# 2020_Light_sensor_-_Schematic.net
KiCad netlist of a schematic drawn in EasyEDA
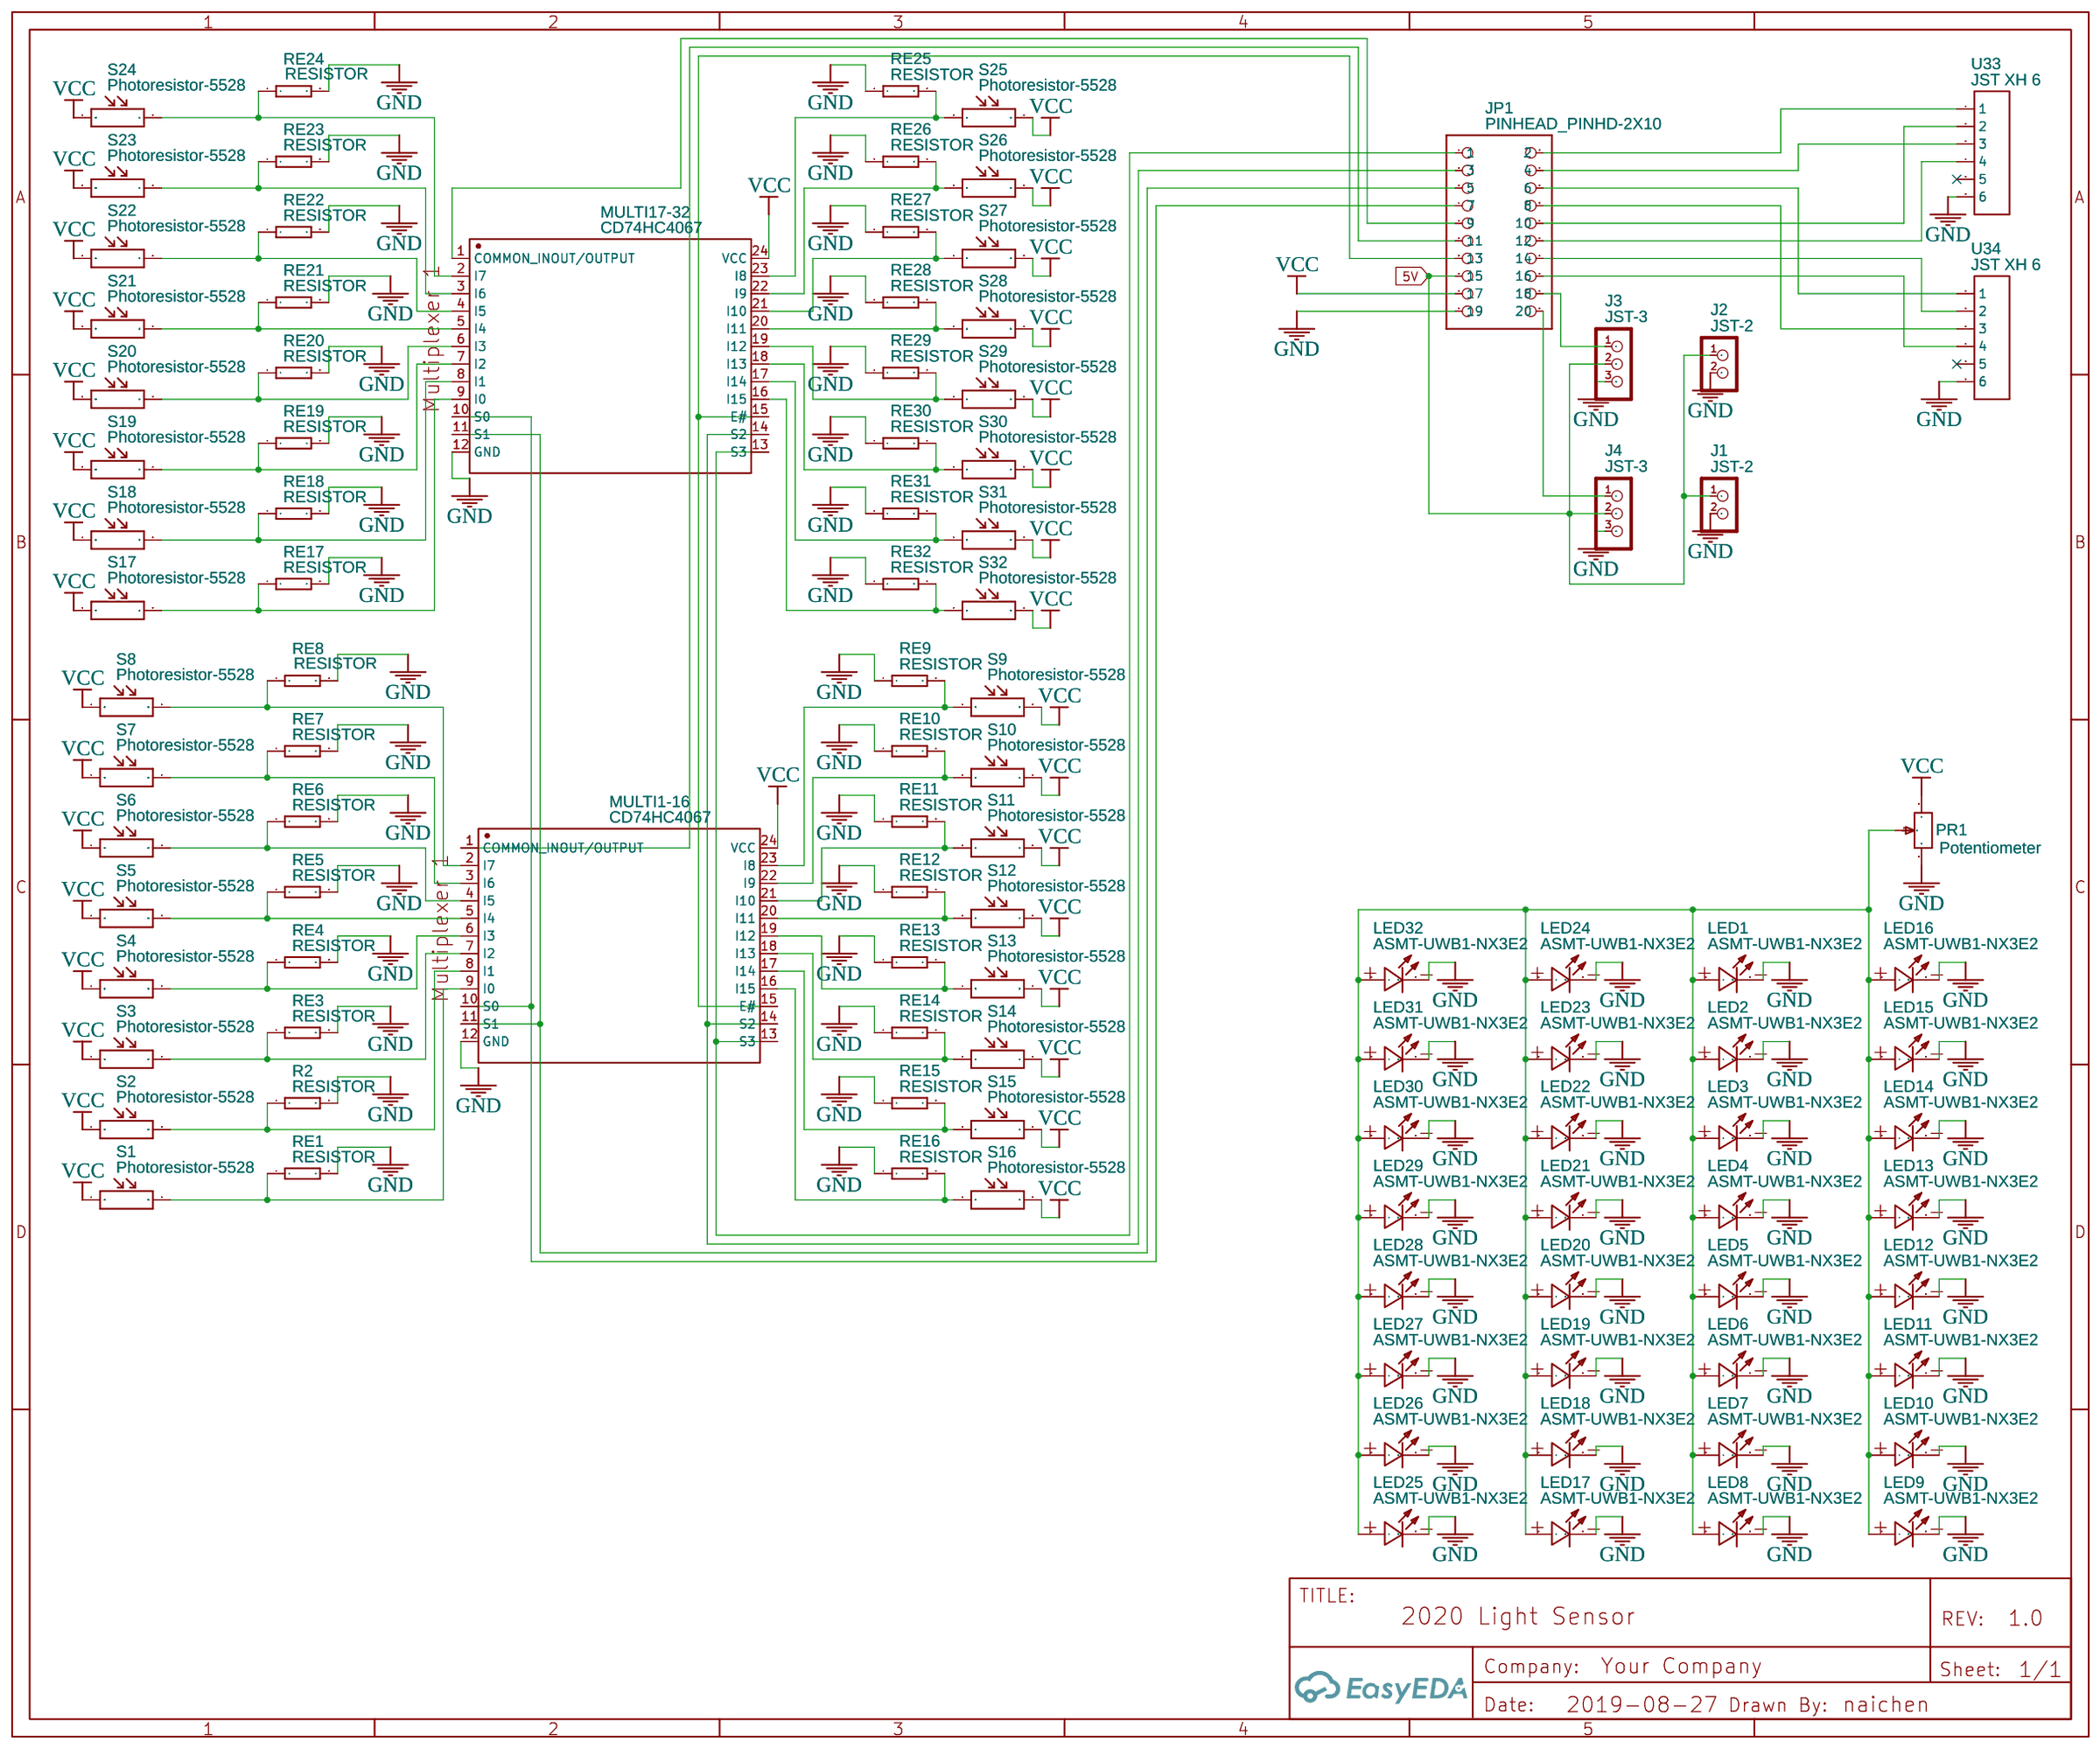
[diagram p0: schematic sheet]

(export (version "E")
  (design (tool "Eeschema 10.0.6"))
  (components
    (comp (ref "J1") (value "JST-2") (libsource (lib "") (part "JST-2")))
    (comp (ref "J2") (value "JST-2") (libsource (lib "") (part "JST-2")))
    (comp (ref "J3") (value "JST-3") (libsource (lib "") (part "JST-3")))
    (comp (ref "J4") (value "JST-3") (libsource (lib "") (part "JST-3")))
    (comp (ref "JP1") (value "PINHEAD_PINHD-2X10") (libsource (lib "") (part "Unknown_845_125")))
    (comp (ref "LED1")
      (value "ASMT-UWB1-NX3E2")
      (fields
        (field (name "BOM_Manufacturer Part") "ASMT-BG20-AS000")
        (field (name "BOM_Supplier Part") "C188684")
      )
      (libsource (lib "") (part "Unknown_975_550"))
    )
    (comp (ref "LED2")
      (value "ASMT-UWB1-NX3E2")
      (fields
        (field (name "BOM_Manufacturer Part") "ASMT-BG20-AS000")
        (field (name "BOM_Supplier Part") "C188684")
      )
      (libsource (lib "") (part "Unknown_975_595"))
    )
    (comp (ref "LED3")
      (value "ASMT-UWB1-NX3E2")
      (fields
        (field (name "BOM_Manufacturer Part") "ASMT-BG20-AS000")
        (field (name "BOM_Supplier Part") "C188684")
      )
      (libsource (lib "") (part "Unknown_975_640"))
    )
    (comp (ref "LED4")
      (value "ASMT-UWB1-NX3E2")
      (fields
        (field (name "BOM_Manufacturer Part") "ASMT-BG20-AS000")
        (field (name "BOM_Supplier Part") "C188684")
      )
      (libsource (lib "") (part "Unknown_975_685"))
    )
    (comp (ref "LED5")
      (value "ASMT-UWB1-NX3E2")
      (fields
        (field (name "BOM_Manufacturer Part") "ASMT-BG20-AS000")
        (field (name "BOM_Supplier Part") "C188684")
      )
      (libsource (lib "") (part "Unknown_975_730"))
    )
    (comp (ref "LED6")
      (value "ASMT-UWB1-NX3E2")
      (fields
        (field (name "BOM_Manufacturer Part") "ASMT-BG20-AS000")
        (field (name "BOM_Supplier Part") "C188684")
      )
      (libsource (lib "") (part "Unknown_975_775"))
    )
    (comp (ref "LED7")
      (value "ASMT-UWB1-NX3E2")
      (fields
        (field (name "BOM_Manufacturer Part") "ASMT-BG20-AS000")
        (field (name "BOM_Supplier Part") "C188684")
      )
      (libsource (lib "") (part "Unknown_975_820"))
    )
    (comp (ref "LED8")
      (value "ASMT-UWB1-NX3E2")
      (fields
        (field (name "BOM_Manufacturer Part") "ASMT-BG20-AS000")
        (field (name "BOM_Supplier Part") "C188684")
      )
      (libsource (lib "") (part "Unknown_975_865"))
    )
    (comp (ref "LED9")
      (value "ASMT-UWB1-NX3E2")
      (fields
        (field (name "BOM_Manufacturer Part") "ASMT-BG20-AS000")
        (field (name "BOM_Supplier Part") "C188684")
      )
      (libsource (lib "") (part "Unknown_1075_865"))
    )
    (comp (ref "LED10")
      (value "ASMT-UWB1-NX3E2")
      (fields
        (field (name "BOM_Manufacturer Part") "ASMT-BG20-AS000")
        (field (name "BOM_Supplier Part") "C188684")
      )
      (libsource (lib "") (part "Unknown_1075_820"))
    )
    (comp (ref "LED11")
      (value "ASMT-UWB1-NX3E2")
      (fields
        (field (name "BOM_Manufacturer Part") "ASMT-BG20-AS000")
        (field (name "BOM_Supplier Part") "C188684")
      )
      (libsource (lib "") (part "Unknown_1075_775"))
    )
    (comp (ref "LED12")
      (value "ASMT-UWB1-NX3E2")
      (fields
        (field (name "BOM_Manufacturer Part") "ASMT-BG20-AS000")
        (field (name "BOM_Supplier Part") "C188684")
      )
      (libsource (lib "") (part "Unknown_1075_730"))
    )
    (comp (ref "LED13")
      (value "ASMT-UWB1-NX3E2")
      (fields
        (field (name "BOM_Manufacturer Part") "ASMT-BG20-AS000")
        (field (name "BOM_Supplier Part") "C188684")
      )
      (libsource (lib "") (part "Unknown_1075_685"))
    )
    (comp (ref "LED14")
      (value "ASMT-UWB1-NX3E2")
      (fields
        (field (name "BOM_Manufacturer Part") "ASMT-BG20-AS000")
        (field (name "BOM_Supplier Part") "C188684")
      )
      (libsource (lib "") (part "Unknown_1075_640"))
    )
    (comp (ref "LED15")
      (value "ASMT-UWB1-NX3E2")
      (fields
        (field (name "BOM_Manufacturer Part") "ASMT-BG20-AS000")
        (field (name "BOM_Supplier Part") "C188684")
      )
      (libsource (lib "") (part "Unknown_1075_595"))
    )
    (comp (ref "LED16")
      (value "ASMT-UWB1-NX3E2")
      (fields
        (field (name "BOM_Manufacturer Part") "ASMT-BG20-AS000")
        (field (name "BOM_Supplier Part") "C188684")
      )
      (libsource (lib "") (part "Unknown_1075_550"))
    )
    (comp (ref "LED17")
      (value "ASMT-UWB1-NX3E2")
      (fields
        (field (name "BOM_Manufacturer Part") "ASMT-BG20-AS000")
        (field (name "BOM_Supplier Part") "C188684")
      )
      (libsource (lib "") (part "Unknown_880_865"))
    )
    (comp (ref "LED18")
      (value "ASMT-UWB1-NX3E2")
      (fields
        (field (name "BOM_Manufacturer Part") "ASMT-BG20-AS000")
        (field (name "BOM_Supplier Part") "C188684")
      )
      (libsource (lib "") (part "Unknown_880_820"))
    )
    (comp (ref "LED19")
      (value "ASMT-UWB1-NX3E2")
      (fields
        (field (name "BOM_Manufacturer Part") "ASMT-BG20-AS000")
        (field (name "BOM_Supplier Part") "C188684")
      )
      (libsource (lib "") (part "Unknown_880_775"))
    )
    (comp (ref "LED20")
      (value "ASMT-UWB1-NX3E2")
      (fields
        (field (name "BOM_Manufacturer Part") "ASMT-BG20-AS000")
        (field (name "BOM_Supplier Part") "C188684")
      )
      (libsource (lib "") (part "Unknown_880_730"))
    )
    (comp (ref "LED21")
      (value "ASMT-UWB1-NX3E2")
      (fields
        (field (name "BOM_Manufacturer Part") "ASMT-BG20-AS000")
        (field (name "BOM_Supplier Part") "C188684")
      )
      (libsource (lib "") (part "Unknown_880_685"))
    )
    (comp (ref "LED22")
      (value "ASMT-UWB1-NX3E2")
      (fields
        (field (name "BOM_Manufacturer Part") "ASMT-BG20-AS000")
        (field (name "BOM_Supplier Part") "C188684")
      )
      (libsource (lib "") (part "Unknown_880_640"))
    )
    (comp (ref "LED23")
      (value "ASMT-UWB1-NX3E2")
      (fields
        (field (name "BOM_Manufacturer Part") "ASMT-BG20-AS000")
        (field (name "BOM_Supplier Part") "C188684")
      )
      (libsource (lib "") (part "Unknown_880_595"))
    )
    (comp (ref "LED24")
      (value "ASMT-UWB1-NX3E2")
      (fields
        (field (name "BOM_Manufacturer Part") "ASMT-BG20-AS000")
        (field (name "BOM_Supplier Part") "C188684")
      )
      (libsource (lib "") (part "Unknown_880_550"))
    )
    (comp (ref "LED25")
      (value "ASMT-UWB1-NX3E2")
      (fields
        (field (name "BOM_Manufacturer Part") "ASMT-BG20-AS000")
        (field (name "BOM_Supplier Part") "C188684")
      )
      (libsource (lib "") (part "Unknown_785_865"))
    )
    (comp (ref "LED26")
      (value "ASMT-UWB1-NX3E2")
      (fields
        (field (name "BOM_Manufacturer Part") "ASMT-BG20-AS000")
        (field (name "BOM_Supplier Part") "C188684")
      )
      (libsource (lib "") (part "Unknown_785_820"))
    )
    (comp (ref "LED27")
      (value "ASMT-UWB1-NX3E2")
      (fields
        (field (name "BOM_Manufacturer Part") "ASMT-BG20-AS000")
        (field (name "BOM_Supplier Part") "C188684")
      )
      (libsource (lib "") (part "Unknown_785_775"))
    )
    (comp (ref "LED28")
      (value "ASMT-UWB1-NX3E2")
      (fields
        (field (name "BOM_Manufacturer Part") "ASMT-BG20-AS000")
        (field (name "BOM_Supplier Part") "C188684")
      )
      (libsource (lib "") (part "Unknown_785_730"))
    )
    (comp (ref "LED29")
      (value "ASMT-UWB1-NX3E2")
      (fields
        (field (name "BOM_Manufacturer Part") "ASMT-BG20-AS000")
        (field (name "BOM_Supplier Part") "C188684")
      )
      (libsource (lib "") (part "Unknown_785_685"))
    )
    (comp (ref "LED30")
      (value "ASMT-UWB1-NX3E2")
      (fields
        (field (name "BOM_Manufacturer Part") "ASMT-BG20-AS000")
        (field (name "BOM_Supplier Part") "C188684")
      )
      (libsource (lib "") (part "Unknown_785_640"))
    )
    (comp (ref "LED31")
      (value "ASMT-UWB1-NX3E2")
      (fields
        (field (name "BOM_Manufacturer Part") "ASMT-BG20-AS000")
        (field (name "BOM_Supplier Part") "C188684")
      )
      (libsource (lib "") (part "Unknown_785_595"))
    )
    (comp (ref "LED32")
      (value "ASMT-UWB1-NX3E2")
      (fields
        (field (name "BOM_Manufacturer Part") "ASMT-BG20-AS000")
        (field (name "BOM_Supplier Part") "C188684")
      )
      (libsource (lib "") (part "Unknown_785_550"))
    )
    (comp (ref "MULTI1-16") (value "CD74HC4067") (libsource (lib "") (part "Unknown_345_530")))
    (comp (ref "MULTI17-32") (value "CD74HC4067") (libsource (lib "") (part "Unknown_340_195")))
    (comp (ref "PR1")
      (value "Potentiometer")
      (fields
        (field (name "BOM_Manufacturer Part") "Precision potentiometer 3296W/50ohm")
        (field (name "BOM_Supplier Part") "C21881")
      )
      (libsource (lib "") (part "Unknown_1080_465"))
    )
    (comp (ref "R2") (value "RESISTOR") (libsource (lib "") (part "Unknown_165_620")))
    (comp (ref "RE1") (value "RESISTOR") (libsource (lib "") (part "Unknown_165_660")))
    (comp (ref "RE3") (value "RESISTOR") (libsource (lib "") (part "Unknown_165_580")))
    (comp (ref "RE4") (value "RESISTOR") (libsource (lib "") (part "Unknown_165_540")))
    (comp (ref "RE5") (value "RESISTOR") (libsource (lib "") (part "Unknown_165_500")))
    (comp (ref "RE6") (value "RESISTOR") (libsource (lib "") (part "Unknown_165_460")))
    (comp (ref "RE7") (value "RESISTOR") (libsource (lib "") (part "Unknown_165_420")))
    (comp (ref "RE8") (value "RESISTOR") (libsource (lib "") (part "Unknown_165_380")))
    (comp (ref "RE9") (value "RESISTOR") (libsource (lib "") (part "Unknown_510_380")))
    (comp (ref "RE10") (value "RESISTOR") (libsource (lib "") (part "Unknown_510_420")))
    (comp (ref "RE11") (value "RESISTOR") (libsource (lib "") (part "Unknown_510_460")))
    (comp (ref "RE12") (value "RESISTOR") (libsource (lib "") (part "Unknown_510_500")))
    (comp (ref "RE13") (value "RESISTOR") (libsource (lib "") (part "Unknown_510_540")))
    (comp (ref "RE14") (value "RESISTOR") (libsource (lib "") (part "Unknown_510_580")))
    (comp (ref "RE15") (value "RESISTOR") (libsource (lib "") (part "Unknown_510_620")))
    (comp (ref "RE16") (value "RESISTOR") (libsource (lib "") (part "Unknown_510_660")))
    (comp (ref "RE17") (value "RESISTOR") (libsource (lib "") (part "Unknown_160_325")))
    (comp (ref "RE18") (value "RESISTOR") (libsource (lib "") (part "Unknown_160_285")))
    (comp (ref "RE19") (value "RESISTOR") (libsource (lib "") (part "Unknown_160_245")))
    (comp (ref "RE20") (value "RESISTOR") (libsource (lib "") (part "Unknown_160_205")))
    (comp (ref "RE21") (value "RESISTOR") (libsource (lib "") (part "Unknown_160_165")))
    (comp (ref "RE22") (value "RESISTOR") (libsource (lib "") (part "Unknown_160_125")))
    (comp (ref "RE23") (value "RESISTOR") (libsource (lib "") (part "Unknown_160_85")))
    (comp (ref "RE24") (value "RESISTOR") (libsource (lib "") (part "Unknown_160_45")))
    (comp (ref "RE25") (value "RESISTOR") (libsource (lib "") (part "Unknown_505_45")))
    (comp (ref "RE26") (value "RESISTOR") (libsource (lib "") (part "Unknown_505_85")))
    (comp (ref "RE27") (value "RESISTOR") (libsource (lib "") (part "Unknown_505_125")))
    (comp (ref "RE28") (value "RESISTOR") (libsource (lib "") (part "Unknown_505_165")))
    (comp (ref "RE29") (value "RESISTOR") (libsource (lib "") (part "Unknown_505_205")))
    (comp (ref "RE30") (value "RESISTOR") (libsource (lib "") (part "Unknown_505_245")))
    (comp (ref "RE31") (value "RESISTOR") (libsource (lib "") (part "Unknown_505_285")))
    (comp (ref "RE32") (value "RESISTOR") (libsource (lib "") (part "Unknown_505_325")))
    (comp (ref "S1") (value "Photoresistor-5528") (libsource (lib "") (part "Unknown_65_670")))
    (comp (ref "S2") (value "Photoresistor-5528") (libsource (lib "") (part "Unknown_65_630")))
    (comp (ref "S3") (value "Photoresistor-5528") (libsource (lib "") (part "Unknown_65_590")))
    (comp (ref "S4") (value "Photoresistor-5528") (libsource (lib "") (part "Unknown_65_550")))
    (comp (ref "S5") (value "Photoresistor-5528") (libsource (lib "") (part "Unknown_65_510")))
    (comp (ref "S6") (value "Photoresistor-5528") (libsource (lib "") (part "Unknown_65_470")))
    (comp (ref "S7") (value "Photoresistor-5528") (libsource (lib "") (part "Unknown_65_430")))
    (comp (ref "S8") (value "Photoresistor-5528") (libsource (lib "") (part "Unknown_65_390")))
    (comp (ref "S9") (value "Photoresistor-5528") (libsource (lib "") (part "Unknown_560_390")))
    (comp (ref "S10") (value "Photoresistor-5528") (libsource (lib "") (part "Unknown_560_430")))
    (comp (ref "S11") (value "Photoresistor-5528") (libsource (lib "") (part "Unknown_560_470")))
    (comp (ref "S12") (value "Photoresistor-5528") (libsource (lib "") (part "Unknown_560_510")))
    (comp (ref "S13") (value "Photoresistor-5528") (libsource (lib "") (part "Unknown_560_550")))
    (comp (ref "S14") (value "Photoresistor-5528") (libsource (lib "") (part "Unknown_560_590")))
    (comp (ref "S15") (value "Photoresistor-5528") (libsource (lib "") (part "Unknown_560_630")))
    (comp (ref "S16") (value "Photoresistor-5528") (libsource (lib "") (part "Unknown_560_670")))
    (comp (ref "S17") (value "Photoresistor-5528") (libsource (lib "") (part "Unknown_60_335")))
    (comp (ref "S18") (value "Photoresistor-5528") (libsource (lib "") (part "Unknown_60_295")))
    (comp (ref "S19") (value "Photoresistor-5528") (libsource (lib "") (part "Unknown_60_255")))
    (comp (ref "S20") (value "Photoresistor-5528") (libsource (lib "") (part "Unknown_60_215")))
    (comp (ref "S21") (value "Photoresistor-5528") (libsource (lib "") (part "Unknown_60_175")))
    (comp (ref "S22") (value "Photoresistor-5528") (libsource (lib "") (part "Unknown_60_135")))
    (comp (ref "S23") (value "Photoresistor-5528") (libsource (lib "") (part "Unknown_60_95")))
    (comp (ref "S24") (value "Photoresistor-5528") (libsource (lib "") (part "Unknown_60_55")))
    (comp (ref "S25") (value "Photoresistor-5528") (libsource (lib "") (part "Unknown_555_55")))
    (comp (ref "S26") (value "Photoresistor-5528") (libsource (lib "") (part "Unknown_555_95")))
    (comp (ref "S27") (value "Photoresistor-5528") (libsource (lib "") (part "Unknown_555_135")))
    (comp (ref "S28") (value "Photoresistor-5528") (libsource (lib "") (part "Unknown_555_175")))
    (comp (ref "S29") (value "Photoresistor-5528") (libsource (lib "") (part "Unknown_555_215")))
    (comp (ref "S30") (value "Photoresistor-5528") (libsource (lib "") (part "Unknown_555_255")))
    (comp (ref "S31") (value "Photoresistor-5528") (libsource (lib "") (part "Unknown_555_295")))
    (comp (ref "S32") (value "Photoresistor-5528") (libsource (lib "") (part "Unknown_555_335")))
    (comp (ref "U33")
      (value "JST XH 6")
      (fields (field (name "BOM_Manufacturer Part") "JST_XH CONNECTOR"))
      (libsource (lib "") (part "Unknown_1115_115"))
    )
    (comp (ref "U34")
      (value "JST XH 6")
      (fields (field (name "BOM_Manufacturer Part") "JST_XH CONNECTOR"))
      (libsource (lib "") (part "Unknown_1115_220"))
    )
  )
  (nets
    (net (code "1") (name "5V") (class "Default")
      (node (ref "J1") (pin "1") (pinfunction "1_1") (pintype "unspecified"))
      (node (ref "J2") (pin "1") (pinfunction "1_1") (pintype "unspecified"))
      (node (ref "J3") (pin "2") (pinfunction "2_2") (pintype "unspecified"))
      (node (ref "J4") (pin "2") (pinfunction "2_2") (pintype "unspecified"))
      (node (ref "JP1") (pin "15") (pinfunction "15_15") (pintype "unspecified"))
    )
    (net (code "2") (name "GND") (class "Default")
      (node (ref "J1") (pin "2") (pinfunction "2_2") (pintype "unspecified"))
      (node (ref "J2") (pin "2") (pinfunction "2_2") (pintype "unspecified"))
      (node (ref "J3") (pin "3") (pinfunction "3_3") (pintype "unspecified"))
      (node (ref "J4") (pin "3") (pinfunction "3_3") (pintype "unspecified"))
      (node (ref "JP1") (pin "19") (pinfunction "19_19") (pintype "unspecified"))
      (node (ref "LED1") (pin "2") (pinfunction "C_2") (pintype "unspecified"))
      (node (ref "LED10") (pin "2") (pinfunction "C_2") (pintype "unspecified"))
      (node (ref "LED11") (pin "2") (pinfunction "C_2") (pintype "unspecified"))
      (node (ref "LED12") (pin "2") (pinfunction "C_2") (pintype "unspecified"))
      (node (ref "LED13") (pin "2") (pinfunction "C_2") (pintype "unspecified"))
      (node (ref "LED14") (pin "2") (pinfunction "C_2") (pintype "unspecified"))
      (node (ref "LED15") (pin "2") (pinfunction "C_2") (pintype "unspecified"))
      (node (ref "LED16") (pin "2") (pinfunction "C_2") (pintype "unspecified"))
      (node (ref "LED17") (pin "2") (pinfunction "C_2") (pintype "unspecified"))
      (node (ref "LED18") (pin "2") (pinfunction "C_2") (pintype "unspecified"))
      (node (ref "LED19") (pin "2") (pinfunction "C_2") (pintype "unspecified"))
      (node (ref "LED2") (pin "2") (pinfunction "C_2") (pintype "unspecified"))
      (node (ref "LED20") (pin "2") (pinfunction "C_2") (pintype "unspecified"))
      (node (ref "LED21") (pin "2") (pinfunction "C_2") (pintype "unspecified"))
      (node (ref "LED22") (pin "2") (pinfunction "C_2") (pintype "unspecified"))
      (node (ref "LED23") (pin "2") (pinfunction "C_2") (pintype "unspecified"))
      (node (ref "LED24") (pin "2") (pinfunction "C_2") (pintype "unspecified"))
      (node (ref "LED25") (pin "2") (pinfunction "C_2") (pintype "unspecified"))
      (node (ref "LED26") (pin "2") (pinfunction "C_2") (pintype "unspecified"))
      (node (ref "LED27") (pin "2") (pinfunction "C_2") (pintype "unspecified"))
      (node (ref "LED28") (pin "2") (pinfunction "C_2") (pintype "unspecified"))
      (node (ref "LED29") (pin "2") (pinfunction "C_2") (pintype "unspecified"))
      (node (ref "LED3") (pin "2") (pinfunction "C_2") (pintype "unspecified"))
      (node (ref "LED30") (pin "2") (pinfunction "C_2") (pintype "unspecified"))
      (node (ref "LED31") (pin "2") (pinfunction "C_2") (pintype "unspecified"))
      (node (ref "LED32") (pin "2") (pinfunction "C_2") (pintype "unspecified"))
      (node (ref "LED4") (pin "2") (pinfunction "C_2") (pintype "unspecified"))
      (node (ref "LED5") (pin "2") (pinfunction "C_2") (pintype "unspecified"))
      (node (ref "LED6") (pin "2") (pinfunction "C_2") (pintype "unspecified"))
      (node (ref "LED7") (pin "2") (pinfunction "C_2") (pintype "unspecified"))
      (node (ref "LED8") (pin "2") (pinfunction "C_2") (pintype "unspecified"))
      (node (ref "LED9") (pin "2") (pinfunction "C_2") (pintype "unspecified"))
      (node (ref "MULTI1-16") (pin "12") (pinfunction "GND_12") (pintype "unspecified"))
      (node (ref "MULTI17-32") (pin "12") (pinfunction "GND_12") (pintype "unspecified"))
      (node (ref "PR1") (pin "3") (pinfunction "3_3") (pintype "input"))
      (node (ref "R2") (pin "2") (pinfunction "2_2") (pintype "unspecified"))
      (node (ref "RE1") (pin "2") (pinfunction "2_2") (pintype "unspecified"))
      (node (ref "RE10") (pin "1") (pinfunction "1_1") (pintype "unspecified"))
      (node (ref "RE11") (pin "1") (pinfunction "1_1") (pintype "unspecified"))
      (node (ref "RE12") (pin "1") (pinfunction "1_1") (pintype "unspecified"))
      (node (ref "RE13") (pin "1") (pinfunction "1_1") (pintype "unspecified"))
      (node (ref "RE14") (pin "1") (pinfunction "1_1") (pintype "unspecified"))
      (node (ref "RE15") (pin "1") (pinfunction "1_1") (pintype "unspecified"))
      (node (ref "RE16") (pin "1") (pinfunction "1_1") (pintype "unspecified"))
      (node (ref "RE17") (pin "2") (pinfunction "2_2") (pintype "unspecified"))
      (node (ref "RE18") (pin "2") (pinfunction "2_2") (pintype "unspecified"))
      (node (ref "RE19") (pin "2") (pinfunction "2_2") (pintype "unspecified"))
      (node (ref "RE20") (pin "2") (pinfunction "2_2") (pintype "unspecified"))
      (node (ref "RE21") (pin "2") (pinfunction "2_2") (pintype "unspecified"))
      (node (ref "RE22") (pin "2") (pinfunction "2_2") (pintype "unspecified"))
      (node (ref "RE23") (pin "2") (pinfunction "2_2") (pintype "unspecified"))
      (node (ref "RE24") (pin "2") (pinfunction "2_2") (pintype "unspecified"))
      (node (ref "RE25") (pin "1") (pinfunction "1_1") (pintype "unspecified"))
      (node (ref "RE26") (pin "1") (pinfunction "1_1") (pintype "unspecified"))
      (node (ref "RE27") (pin "1") (pinfunction "1_1") (pintype "unspecified"))
      (node (ref "RE28") (pin "1") (pinfunction "1_1") (pintype "unspecified"))
      (node (ref "RE29") (pin "1") (pinfunction "1_1") (pintype "unspecified"))
      (node (ref "RE3") (pin "2") (pinfunction "2_2") (pintype "unspecified"))
      (node (ref "RE30") (pin "1") (pinfunction "1_1") (pintype "unspecified"))
      (node (ref "RE31") (pin "1") (pinfunction "1_1") (pintype "unspecified"))
      (node (ref "RE32") (pin "1") (pinfunction "1_1") (pintype "unspecified"))
      (node (ref "RE4") (pin "2") (pinfunction "2_2") (pintype "unspecified"))
      (node (ref "RE5") (pin "2") (pinfunction "2_2") (pintype "unspecified"))
      (node (ref "RE6") (pin "2") (pinfunction "2_2") (pintype "unspecified"))
      (node (ref "RE7") (pin "2") (pinfunction "2_2") (pintype "unspecified"))
      (node (ref "RE8") (pin "2") (pinfunction "2_2") (pintype "unspecified"))
      (node (ref "RE9") (pin "1") (pinfunction "1_1") (pintype "unspecified"))
      (node (ref "U33") (pin "6") (pinfunction "6_6") (pintype "unspecified"))
      (node (ref "U34") (pin "6") (pinfunction "6_6") (pintype "unspecified"))
    )
    (net (code "3") (name "Net-(J3-Pad1)") (class "Default")
      (node (ref "J3") (pin "1") (pinfunction "1_1") (pintype "unspecified"))
      (node (ref "JP1") (pin "18") (pinfunction "18_18") (pintype "unspecified"))
    )
    (net (code "4") (name "Net-(J4-Pad1)") (class "Default")
      (node (ref "J4") (pin "1") (pinfunction "1_1") (pintype "unspecified"))
      (node (ref "JP1") (pin "20") (pinfunction "20_20") (pintype "unspecified"))
    )
    (net (code "5") (name "Net-(JP1-Pad2)") (class "Default")
      (node (ref "JP1") (pin "2") (pinfunction "2_2") (pintype "unspecified"))
      (node (ref "U33") (pin "1") (pinfunction "1_1") (pintype "unspecified"))
    )
    (net (code "6") (name "Net-(JP1-Pad4)") (class "Default")
      (node (ref "JP1") (pin "4") (pinfunction "4_4") (pintype "unspecified"))
      (node (ref "U33") (pin "3") (pinfunction "3_3") (pintype "unspecified"))
    )
    (net (code "7") (name "Net-(JP1-Pad6)") (class "Default")
      (node (ref "JP1") (pin "6") (pinfunction "6_6") (pintype "unspecified"))
      (node (ref "U34") (pin "1") (pinfunction "1_1") (pintype "unspecified"))
    )
    (net (code "8") (name "Net-(JP1-Pad8)") (class "Default")
      (node (ref "JP1") (pin "8") (pinfunction "8_8") (pintype "unspecified"))
      (node (ref "U34") (pin "3") (pinfunction "3_3") (pintype "unspecified"))
    )
    (net (code "9") (name "Net-(JP1-Pad10)") (class "Default")
      (node (ref "JP1") (pin "10") (pinfunction "10_10") (pintype "unspecified"))
      (node (ref "U33") (pin "2") (pinfunction "2_2") (pintype "unspecified"))
    )
    (net (code "10") (name "Net-(JP1-Pad12)") (class "Default")
      (node (ref "JP1") (pin "12") (pinfunction "12_12") (pintype "unspecified"))
      (node (ref "U33") (pin "4") (pinfunction "4_4") (pintype "unspecified"))
    )
    (net (code "11") (name "Net-(JP1-Pad14)") (class "Default")
      (node (ref "JP1") (pin "14") (pinfunction "14_14") (pintype "unspecified"))
      (node (ref "U34") (pin "2") (pinfunction "2_2") (pintype "unspecified"))
    )
    (net (code "12") (name "Net-(JP1-Pad16)") (class "Default")
      (node (ref "JP1") (pin "16") (pinfunction "16_16") (pintype "unspecified"))
      (node (ref "U34") (pin "4") (pinfunction "4_4") (pintype "unspecified"))
    )
    (net (code "13") (name "Net-(LED1-A)") (class "Default")
      (node (ref "LED1") (pin "1") (pinfunction "A_1") (pintype "unspecified"))
      (node (ref "LED10") (pin "1") (pinfunction "A_1") (pintype "unspecified"))
      (node (ref "LED11") (pin "1") (pinfunction "A_1") (pintype "unspecified"))
      (node (ref "LED12") (pin "1") (pinfunction "A_1") (pintype "unspecified"))
      (node (ref "LED13") (pin "1") (pinfunction "A_1") (pintype "unspecified"))
      (node (ref "LED14") (pin "1") (pinfunction "A_1") (pintype "unspecified"))
      (node (ref "LED15") (pin "1") (pinfunction "A_1") (pintype "unspecified"))
      (node (ref "LED16") (pin "1") (pinfunction "A_1") (pintype "unspecified"))
      (node (ref "LED17") (pin "1") (pinfunction "A_1") (pintype "unspecified"))
      (node (ref "LED18") (pin "1") (pinfunction "A_1") (pintype "unspecified"))
      (node (ref "LED19") (pin "1") (pinfunction "A_1") (pintype "unspecified"))
      (node (ref "LED2") (pin "1") (pinfunction "A_1") (pintype "unspecified"))
      (node (ref "LED20") (pin "1") (pinfunction "A_1") (pintype "unspecified"))
      (node (ref "LED21") (pin "1") (pinfunction "A_1") (pintype "unspecified"))
      (node (ref "LED22") (pin "1") (pinfunction "A_1") (pintype "unspecified"))
      (node (ref "LED23") (pin "1") (pinfunction "A_1") (pintype "unspecified"))
      (node (ref "LED24") (pin "1") (pinfunction "A_1") (pintype "unspecified"))
      (node (ref "LED25") (pin "1") (pinfunction "A_1") (pintype "unspecified"))
      (node (ref "LED26") (pin "1") (pinfunction "A_1") (pintype "unspecified"))
      (node (ref "LED27") (pin "1") (pinfunction "A_1") (pintype "unspecified"))
      (node (ref "LED28") (pin "1") (pinfunction "A_1") (pintype "unspecified"))
      (node (ref "LED29") (pin "1") (pinfunction "A_1") (pintype "unspecified"))
      (node (ref "LED3") (pin "1") (pinfunction "A_1") (pintype "unspecified"))
      (node (ref "LED30") (pin "1") (pinfunction "A_1") (pintype "unspecified"))
      (node (ref "LED31") (pin "1") (pinfunction "A_1") (pintype "unspecified"))
      (node (ref "LED32") (pin "1") (pinfunction "A_1") (pintype "unspecified"))
      (node (ref "LED4") (pin "1") (pinfunction "A_1") (pintype "unspecified"))
      (node (ref "LED5") (pin "1") (pinfunction "A_1") (pintype "unspecified"))
      (node (ref "LED6") (pin "1") (pinfunction "A_1") (pintype "unspecified"))
      (node (ref "LED7") (pin "1") (pinfunction "A_1") (pintype "unspecified"))
      (node (ref "LED8") (pin "1") (pinfunction "A_1") (pintype "unspecified"))
      (node (ref "LED9") (pin "1") (pinfunction "A_1") (pintype "unspecified"))
      (node (ref "PR1") (pin "2") (pinfunction "2_2") (pintype "input"))
    )
    (net (code "14") (name "Net-(MULTI1-16-COMMON_INOUT{slash}OUTPUT)") (class "Default")
      (node (ref "JP1") (pin "11") (pinfunction "11_11") (pintype "unspecified"))
      (node (ref "MULTI1-16") (pin "1") (pinfunction "COMMON_INOUT/OUTPUT_1") (pintype "unspecified"))
    )
    (net (code "15") (name "Net-(MULTI1-16-E#)") (class "Default")
      (node (ref "JP1") (pin "13") (pinfunction "13_13") (pintype "unspecified"))
      (node (ref "MULTI1-16") (pin "15") (pinfunction "E#_15") (pintype "unspecified"))
      (node (ref "MULTI17-32") (pin "15") (pinfunction "E#_15") (pintype "unspecified"))
    )
    (net (code "16") (name "Net-(MULTI1-16-I0)") (class "Default")
      (node (ref "MULTI1-16") (pin "9") (pinfunction "I0_9") (pintype "unspecified"))
      (node (ref "RE1") (pin "1") (pinfunction "1_1") (pintype "unspecified"))
      (node (ref "S1") (pin "2") (pinfunction "P$2_2") (pintype "unspecified"))
    )
    (net (code "17") (name "Net-(MULTI1-16-I1)") (class "Default")
      (node (ref "MULTI1-16") (pin "8") (pinfunction "I1_8") (pintype "unspecified"))
      (node (ref "R2") (pin "1") (pinfunction "1_1") (pintype "unspecified"))
      (node (ref "S2") (pin "2") (pinfunction "P$2_2") (pintype "unspecified"))
    )
    (net (code "18") (name "Net-(MULTI1-16-I2)") (class "Default")
      (node (ref "MULTI1-16") (pin "7") (pinfunction "I2_7") (pintype "unspecified"))
      (node (ref "RE3") (pin "1") (pinfunction "1_1") (pintype "unspecified"))
      (node (ref "S3") (pin "2") (pinfunction "P$2_2") (pintype "unspecified"))
    )
    (net (code "19") (name "Net-(MULTI1-16-I3)") (class "Default")
      (node (ref "MULTI1-16") (pin "6") (pinfunction "I3_6") (pintype "unspecified"))
      (node (ref "RE4") (pin "1") (pinfunction "1_1") (pintype "unspecified"))
      (node (ref "S4") (pin "2") (pinfunction "P$2_2") (pintype "unspecified"))
    )
    (net (code "20") (name "Net-(MULTI1-16-I4)") (class "Default")
      (node (ref "MULTI1-16") (pin "5") (pinfunction "I4_5") (pintype "unspecified"))
      (node (ref "RE5") (pin "1") (pinfunction "1_1") (pintype "unspecified"))
      (node (ref "S5") (pin "2") (pinfunction "P$2_2") (pintype "unspecified"))
    )
    (net (code "21") (name "Net-(MULTI1-16-I5)") (class "Default")
      (node (ref "MULTI1-16") (pin "4") (pinfunction "I5_4") (pintype "unspecified"))
      (node (ref "RE6") (pin "1") (pinfunction "1_1") (pintype "unspecified"))
      (node (ref "S6") (pin "2") (pinfunction "P$2_2") (pintype "unspecified"))
    )
    (net (code "22") (name "Net-(MULTI1-16-I6)") (class "Default")
      (node (ref "MULTI1-16") (pin "3") (pinfunction "I6_3") (pintype "unspecified"))
      (node (ref "RE7") (pin "1") (pinfunction "1_1") (pintype "unspecified"))
      (node (ref "S7") (pin "2") (pinfunction "P$2_2") (pintype "unspecified"))
    )
    (net (code "23") (name "Net-(MULTI1-16-I7)") (class "Default")
      (node (ref "MULTI1-16") (pin "2") (pinfunction "I7_2") (pintype "unspecified"))
      (node (ref "RE8") (pin "1") (pinfunction "1_1") (pintype "unspecified"))
      (node (ref "S8") (pin "2") (pinfunction "P$2_2") (pintype "unspecified"))
    )
    (net (code "24") (name "Net-(MULTI1-16-I8)") (class "Default")
      (node (ref "MULTI1-16") (pin "23") (pinfunction "I8_23") (pintype "unspecified"))
      (node (ref "RE9") (pin "2") (pinfunction "2_2") (pintype "unspecified"))
      (node (ref "S9") (pin "1") (pinfunction "P$1_1") (pintype "unspecified"))
    )
    (net (code "25") (name "Net-(MULTI1-16-I9)") (class "Default")
      (node (ref "MULTI1-16") (pin "22") (pinfunction "I9_22") (pintype "unspecified"))
      (node (ref "RE10") (pin "2") (pinfunction "2_2") (pintype "unspecified"))
      (node (ref "S10") (pin "1") (pinfunction "P$1_1") (pintype "unspecified"))
    )
    (net (code "26") (name "Net-(MULTI1-16-I10)") (class "Default")
      (node (ref "MULTI1-16") (pin "21") (pinfunction "I10_21") (pintype "unspecified"))
      (node (ref "RE11") (pin "2") (pinfunction "2_2") (pintype "unspecified"))
      (node (ref "S11") (pin "1") (pinfunction "P$1_1") (pintype "unspecified"))
    )
    (net (code "27") (name "Net-(MULTI1-16-I11)") (class "Default")
      (node (ref "MULTI1-16") (pin "20") (pinfunction "I11_20") (pintype "unspecified"))
      (node (ref "RE12") (pin "2") (pinfunction "2_2") (pintype "unspecified"))
      (node (ref "S12") (pin "1") (pinfunction "P$1_1") (pintype "unspecified"))
    )
    (net (code "28") (name "Net-(MULTI1-16-I12)") (class "Default")
      (node (ref "MULTI1-16") (pin "19") (pinfunction "I12_19") (pintype "unspecified"))
      (node (ref "RE13") (pin "2") (pinfunction "2_2") (pintype "unspecified"))
      (node (ref "S13") (pin "1") (pinfunction "P$1_1") (pintype "unspecified"))
    )
    (net (code "29") (name "Net-(MULTI1-16-I13)") (class "Default")
      (node (ref "MULTI1-16") (pin "18") (pinfunction "I13_18") (pintype "unspecified"))
      (node (ref "RE14") (pin "2") (pinfunction "2_2") (pintype "unspecified"))
      (node (ref "S14") (pin "1") (pinfunction "P$1_1") (pintype "unspecified"))
    )
    (net (code "30") (name "Net-(MULTI1-16-I14)") (class "Default")
      (node (ref "MULTI1-16") (pin "17") (pinfunction "I14_17") (pintype "unspecified"))
      (node (ref "RE15") (pin "2") (pinfunction "2_2") (pintype "unspecified"))
      (node (ref "S15") (pin "1") (pinfunction "P$1_1") (pintype "unspecified"))
    )
    (net (code "31") (name "Net-(MULTI1-16-I15)") (class "Default")
      (node (ref "MULTI1-16") (pin "16") (pinfunction "I15_16") (pintype "unspecified"))
      (node (ref "RE16") (pin "2") (pinfunction "2_2") (pintype "unspecified"))
      (node (ref "S16") (pin "1") (pinfunction "P$1_1") (pintype "unspecified"))
    )
    (net (code "32") (name "Net-(MULTI1-16-S0)") (class "Default")
      (node (ref "JP1") (pin "7") (pinfunction "7_7") (pintype "unspecified"))
      (node (ref "MULTI1-16") (pin "10") (pinfunction "S0_10") (pintype "unspecified"))
      (node (ref "MULTI17-32") (pin "10") (pinfunction "S0_10") (pintype "unspecified"))
    )
    (net (code "33") (name "Net-(MULTI1-16-S1)") (class "Default")
      (node (ref "JP1") (pin "5") (pinfunction "5_5") (pintype "unspecified"))
      (node (ref "MULTI1-16") (pin "11") (pinfunction "S1_11") (pintype "unspecified"))
      (node (ref "MULTI17-32") (pin "11") (pinfunction "S1_11") (pintype "unspecified"))
    )
    (net (code "34") (name "Net-(MULTI1-16-S2)") (class "Default")
      (node (ref "JP1") (pin "3") (pinfunction "3_3") (pintype "unspecified"))
      (node (ref "MULTI1-16") (pin "14") (pinfunction "S2_14") (pintype "unspecified"))
      (node (ref "MULTI17-32") (pin "14") (pinfunction "S2_14") (pintype "unspecified"))
    )
    (net (code "35") (name "Net-(MULTI1-16-S3)") (class "Default")
      (node (ref "JP1") (pin "1") (pinfunction "1_1") (pintype "unspecified"))
      (node (ref "MULTI1-16") (pin "13") (pinfunction "S3_13") (pintype "unspecified"))
      (node (ref "MULTI17-32") (pin "13") (pinfunction "S3_13") (pintype "unspecified"))
    )
    (net (code "36") (name "Net-(MULTI17-32-COMMON_INOUT{slash}OUTPUT)") (class "Default")
      (node (ref "JP1") (pin "9") (pinfunction "9_9") (pintype "unspecified"))
      (node (ref "MULTI17-32") (pin "1") (pinfunction "COMMON_INOUT/OUTPUT_1") (pintype "unspecified"))
    )
    (net (code "37") (name "Net-(MULTI17-32-I0)") (class "Default")
      (node (ref "MULTI17-32") (pin "9") (pinfunction "I0_9") (pintype "unspecified"))
      (node (ref "RE17") (pin "1") (pinfunction "1_1") (pintype "unspecified"))
      (node (ref "S17") (pin "2") (pinfunction "P$2_2") (pintype "unspecified"))
    )
    (net (code "38") (name "Net-(MULTI17-32-I1)") (class "Default")
      (node (ref "MULTI17-32") (pin "8") (pinfunction "I1_8") (pintype "unspecified"))
      (node (ref "RE18") (pin "1") (pinfunction "1_1") (pintype "unspecified"))
      (node (ref "S18") (pin "2") (pinfunction "P$2_2") (pintype "unspecified"))
    )
    (net (code "39") (name "Net-(MULTI17-32-I2)") (class "Default")
      (node (ref "MULTI17-32") (pin "7") (pinfunction "I2_7") (pintype "unspecified"))
      (node (ref "RE19") (pin "1") (pinfunction "1_1") (pintype "unspecified"))
      (node (ref "S19") (pin "2") (pinfunction "P$2_2") (pintype "unspecified"))
    )
    (net (code "40") (name "Net-(MULTI17-32-I3)") (class "Default")
      (node (ref "MULTI17-32") (pin "6") (pinfunction "I3_6") (pintype "unspecified"))
      (node (ref "RE20") (pin "1") (pinfunction "1_1") (pintype "unspecified"))
      (node (ref "S20") (pin "2") (pinfunction "P$2_2") (pintype "unspecified"))
    )
    (net (code "41") (name "Net-(MULTI17-32-I4)") (class "Default")
      (node (ref "MULTI17-32") (pin "5") (pinfunction "I4_5") (pintype "unspecified"))
      (node (ref "RE21") (pin "1") (pinfunction "1_1") (pintype "unspecified"))
      (node (ref "S21") (pin "2") (pinfunction "P$2_2") (pintype "unspecified"))
    )
    (net (code "42") (name "Net-(MULTI17-32-I5)") (class "Default")
      (node (ref "MULTI17-32") (pin "4") (pinfunction "I5_4") (pintype "unspecified"))
      (node (ref "RE22") (pin "1") (pinfunction "1_1") (pintype "unspecified"))
      (node (ref "S22") (pin "2") (pinfunction "P$2_2") (pintype "unspecified"))
    )
    (net (code "43") (name "Net-(MULTI17-32-I6)") (class "Default")
      (node (ref "MULTI17-32") (pin "3") (pinfunction "I6_3") (pintype "unspecified"))
      (node (ref "RE23") (pin "1") (pinfunction "1_1") (pintype "unspecified"))
      (node (ref "S23") (pin "2") (pinfunction "P$2_2") (pintype "unspecified"))
    )
    (net (code "44") (name "Net-(MULTI17-32-I7)") (class "Default")
      (node (ref "MULTI17-32") (pin "2") (pinfunction "I7_2") (pintype "unspecified"))
      (node (ref "RE24") (pin "1") (pinfunction "1_1") (pintype "unspecified"))
      (node (ref "S24") (pin "2") (pinfunction "P$2_2") (pintype "unspecified"))
    )
    (net (code "45") (name "Net-(MULTI17-32-I8)") (class "Default")
      (node (ref "MULTI17-32") (pin "23") (pinfunction "I8_23") (pintype "unspecified"))
      (node (ref "RE25") (pin "2") (pinfunction "2_2") (pintype "unspecified"))
      (node (ref "S25") (pin "1") (pinfunction "P$1_1") (pintype "unspecified"))
    )
    (net (code "46") (name "Net-(MULTI17-32-I9)") (class "Default")
      (node (ref "MULTI17-32") (pin "22") (pinfunction "I9_22") (pintype "unspecified"))
      (node (ref "RE26") (pin "2") (pinfunction "2_2") (pintype "unspecified"))
      (node (ref "S26") (pin "1") (pinfunction "P$1_1") (pintype "unspecified"))
    )
    (net (code "47") (name "Net-(MULTI17-32-I10)") (class "Default")
      (node (ref "MULTI17-32") (pin "21") (pinfunction "I10_21") (pintype "unspecified"))
      (node (ref "RE27") (pin "2") (pinfunction "2_2") (pintype "unspecified"))
      (node (ref "S27") (pin "1") (pinfunction "P$1_1") (pintype "unspecified"))
    )
    (net (code "48") (name "Net-(MULTI17-32-I11)") (class "Default")
      (node (ref "MULTI17-32") (pin "20") (pinfunction "I11_20") (pintype "unspecified"))
      (node (ref "RE28") (pin "2") (pinfunction "2_2") (pintype "unspecified"))
      (node (ref "S28") (pin "1") (pinfunction "P$1_1") (pintype "unspecified"))
    )
    (net (code "49") (name "Net-(MULTI17-32-I12)") (class "Default")
      (node (ref "MULTI17-32") (pin "19") (pinfunction "I12_19") (pintype "unspecified"))
      (node (ref "RE29") (pin "2") (pinfunction "2_2") (pintype "unspecified"))
      (node (ref "S29") (pin "1") (pinfunction "P$1_1") (pintype "unspecified"))
    )
    (net (code "50") (name "Net-(MULTI17-32-I13)") (class "Default")
      (node (ref "MULTI17-32") (pin "18") (pinfunction "I13_18") (pintype "unspecified"))
      (node (ref "RE30") (pin "2") (pinfunction "2_2") (pintype "unspecified"))
      (node (ref "S30") (pin "1") (pinfunction "P$1_1") (pintype "unspecified"))
    )
    (net (code "51") (name "Net-(MULTI17-32-I14)") (class "Default")
      (node (ref "MULTI17-32") (pin "17") (pinfunction "I14_17") (pintype "unspecified"))
      (node (ref "RE31") (pin "2") (pinfunction "2_2") (pintype "unspecified"))
      (node (ref "S31") (pin "1") (pinfunction "P$1_1") (pintype "unspecified"))
    )
    (net (code "52") (name "Net-(MULTI17-32-I15)") (class "Default")
      (node (ref "MULTI17-32") (pin "16") (pinfunction "I15_16") (pintype "unspecified"))
      (node (ref "RE32") (pin "2") (pinfunction "2_2") (pintype "unspecified"))
      (node (ref "S32") (pin "1") (pinfunction "P$1_1") (pintype "unspecified"))
    )
    (net (code "53") (name "VCC") (class "Default")
      (node (ref "JP1") (pin "17") (pinfunction "17_17") (pintype "unspecified"))
      (node (ref "MULTI1-16") (pin "24") (pinfunction "VCC_24") (pintype "unspecified"))
      (node (ref "MULTI17-32") (pin "24") (pinfunction "VCC_24") (pintype "unspecified"))
      (node (ref "PR1") (pin "1") (pinfunction "1_1") (pintype "input"))
      (node (ref "S1") (pin "1") (pinfunction "P$1_1") (pintype "unspecified"))
      (node (ref "S10") (pin "2") (pinfunction "P$2_2") (pintype "unspecified"))
      (node (ref "S11") (pin "2") (pinfunction "P$2_2") (pintype "unspecified"))
      (node (ref "S12") (pin "2") (pinfunction "P$2_2") (pintype "unspecified"))
      (node (ref "S13") (pin "2") (pinfunction "P$2_2") (pintype "unspecified"))
      (node (ref "S14") (pin "2") (pinfunction "P$2_2") (pintype "unspecified"))
      (node (ref "S15") (pin "2") (pinfunction "P$2_2") (pintype "unspecified"))
      (node (ref "S16") (pin "2") (pinfunction "P$2_2") (pintype "unspecified"))
      (node (ref "S17") (pin "1") (pinfunction "P$1_1") (pintype "unspecified"))
      (node (ref "S18") (pin "1") (pinfunction "P$1_1") (pintype "unspecified"))
      (node (ref "S19") (pin "1") (pinfunction "P$1_1") (pintype "unspecified"))
      (node (ref "S2") (pin "1") (pinfunction "P$1_1") (pintype "unspecified"))
      (node (ref "S20") (pin "1") (pinfunction "P$1_1") (pintype "unspecified"))
      (node (ref "S21") (pin "1") (pinfunction "P$1_1") (pintype "unspecified"))
      (node (ref "S22") (pin "1") (pinfunction "P$1_1") (pintype "unspecified"))
      (node (ref "S23") (pin "1") (pinfunction "P$1_1") (pintype "unspecified"))
      (node (ref "S24") (pin "1") (pinfunction "P$1_1") (pintype "unspecified"))
      (node (ref "S25") (pin "2") (pinfunction "P$2_2") (pintype "unspecified"))
      (node (ref "S26") (pin "2") (pinfunction "P$2_2") (pintype "unspecified"))
      (node (ref "S27") (pin "2") (pinfunction "P$2_2") (pintype "unspecified"))
      (node (ref "S28") (pin "2") (pinfunction "P$2_2") (pintype "unspecified"))
      (node (ref "S29") (pin "2") (pinfunction "P$2_2") (pintype "unspecified"))
      (node (ref "S3") (pin "1") (pinfunction "P$1_1") (pintype "unspecified"))
      (node (ref "S30") (pin "2") (pinfunction "P$2_2") (pintype "unspecified"))
      (node (ref "S31") (pin "2") (pinfunction "P$2_2") (pintype "unspecified"))
      (node (ref "S32") (pin "2") (pinfunction "P$2_2") (pintype "unspecified"))
      (node (ref "S4") (pin "1") (pinfunction "P$1_1") (pintype "unspecified"))
      (node (ref "S5") (pin "1") (pinfunction "P$1_1") (pintype "unspecified"))
      (node (ref "S6") (pin "1") (pinfunction "P$1_1") (pintype "unspecified"))
      (node (ref "S7") (pin "1") (pinfunction "P$1_1") (pintype "unspecified"))
      (node (ref "S8") (pin "1") (pinfunction "P$1_1") (pintype "unspecified"))
      (node (ref "S9") (pin "2") (pinfunction "P$2_2") (pintype "unspecified"))
    )
    (net (code "54") (name "unconnected-(U33-Pad5)") (class "Default")
      (node (ref "U33") (pin "5") (pinfunction "5_5") (pintype "unspecified+no_connect"))
    )
    (net (code "55") (name "unconnected-(U34-Pad5)") (class "Default")
      (node (ref "U34") (pin "5") (pinfunction "5_5") (pintype "unspecified+no_connect"))
    )
  )
)
